# attiny85_breakout.net
KiCad netlist of a schematic drawn in EAGLE
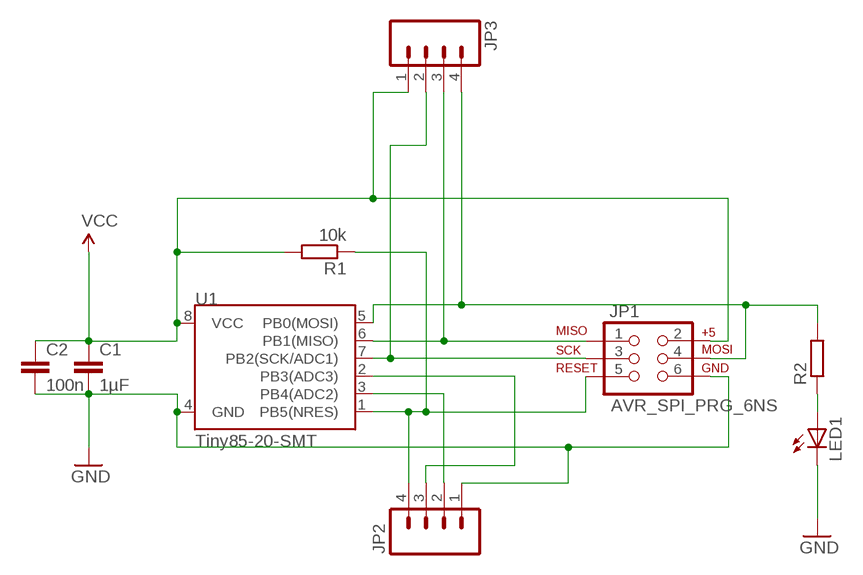
[diagram p0: schematic, sheet 1]

(export (version "E")
  (design (tool "Eeschema 10.0.6"))
  (components
    (comp (ref "C1")
      (value "1µF")
      (footprint "eagle-import:C0805")
      (libsource (lib "eagle-import") (part "C-EUC0805"))
    )
    (comp (ref "C2")
      (value "100n")
      (footprint "eagle-import:C0805")
      (libsource (lib "eagle-import") (part "C-EUC0805"))
    )
    (comp (ref "JP1")
      (value "AVR_SPI_PRG_6NS")
      (footprint "eagle-import:2X3-NS")
      (libsource (lib "eagle-import") (part "AVR_SPI_PRG_6NS"))
    )
    (comp (ref "JP2")
      (value "M04PTH")
      (footprint "eagle-import:1X04")
      (libsource (lib "eagle-import") (part "M04PTH"))
    )
    (comp (ref "JP3")
      (value "M04PTH")
      (footprint "eagle-import:1X04")
      (libsource (lib "eagle-import") (part "M04PTH"))
    )
    (comp (ref "LED1")
      (value "LEDCHIPLED_0805")
      (footprint "eagle-import:CHIPLED_0805")
      (libsource (lib "eagle-import") (part "LEDCHIPLED_0805"))
    )
    (comp (ref "R1")
      (value "10k")
      (footprint "eagle-import:R0805")
      (libsource (lib "eagle-import") (part "R-EU_R0805"))
    )
    (comp (ref "R2")
      (value "R-EU_R0603")
      (footprint "eagle-import:R0603")
      (libsource (lib "eagle-import") (part "R-EU_R0603"))
    )
    (comp (ref "U1")
      (value "Tiny85-20-SMT")
      (footprint "eagle-import:SO08-EIAJ")
      (libsource (lib "eagle-import") (part "ATTINY45TINY85-20-SMT"))
    )
  )
  (nets
    (net (code "1") (name "GND") (class "Default")
      (node (ref "C1") (pin "2") (pinfunction "2_2") (pintype "passive"))
      (node (ref "C2") (pin "2") (pinfunction "2_2") (pintype "passive"))
      (node (ref "JP1") (pin "6") (pinfunction "6_6") (pintype "passive"))
      (node (ref "JP2") (pin "1") (pinfunction "1_1") (pintype "passive"))
      (node (ref "LED1") (pin "C") (pinfunction "C_C") (pintype "passive"))
      (node (ref "U1") (pin "4") (pinfunction "GND_4") (pintype "bidirectional"))
    )
    (net (code "2") (name "Net-(LED1-PadA)") (class "Default")
      (node (ref "LED1") (pin "A") (pinfunction "A_A") (pintype "passive"))
      (node (ref "R2") (pin "1") (pinfunction "1_1") (pintype "passive"))
    )
    (net (code "3") (name "Net-(U1-PB0(MOSI))") (class "Default")
      (node (ref "JP1") (pin "4") (pinfunction "4_4") (pintype "passive"))
      (node (ref "JP3") (pin "4") (pinfunction "4_4") (pintype "passive"))
      (node (ref "R2") (pin "2") (pinfunction "2_2") (pintype "passive"))
      (node (ref "U1") (pin "5") (pinfunction "PB0(MOSI)_5") (pintype "bidirectional"))
    )
    (net (code "4") (name "Net-(U1-PB1(MISO))") (class "Default")
      (node (ref "JP1") (pin "1") (pinfunction "1_1") (pintype "passive"))
      (node (ref "JP3") (pin "3") (pinfunction "3_3") (pintype "passive"))
      (node (ref "U1") (pin "6") (pinfunction "PB1(MISO)_6") (pintype "bidirectional"))
    )
    (net (code "5") (name "Net-(U1-PB2(SCK{slash}ADC1))") (class "Default")
      (node (ref "JP1") (pin "3") (pinfunction "3_3") (pintype "passive"))
      (node (ref "JP3") (pin "2") (pinfunction "2_2") (pintype "passive"))
      (node (ref "U1") (pin "7") (pinfunction "PB2(SCK/ADC1)_7") (pintype "bidirectional"))
    )
    (net (code "6") (name "Net-(U1-PB3(ADC3))") (class "Default")
      (node (ref "JP2") (pin "3") (pinfunction "3_3") (pintype "passive"))
      (node (ref "U1") (pin "2") (pinfunction "PB3(ADC3)_2") (pintype "bidirectional"))
    )
    (net (code "7") (name "Net-(U1-PB4(ADC2))") (class "Default")
      (node (ref "JP2") (pin "2") (pinfunction "2_2") (pintype "passive"))
      (node (ref "U1") (pin "3") (pinfunction "PB4(ADC2)_3") (pintype "bidirectional"))
    )
    (net (code "8") (name "Net-(U1-PB5(NRES))") (class "Default")
      (node (ref "JP1") (pin "5") (pinfunction "5_5") (pintype "passive"))
      (node (ref "JP2") (pin "4") (pinfunction "4_4") (pintype "passive"))
      (node (ref "R1") (pin "1") (pinfunction "1_1") (pintype "passive"))
      (node (ref "U1") (pin "1") (pinfunction "PB5(NRES)_1") (pintype "bidirectional"))
    )
    (net (code "9") (name "VCC") (class "Default")
      (node (ref "C1") (pin "1") (pinfunction "1_1") (pintype "passive"))
      (node (ref "C2") (pin "1") (pinfunction "1_1") (pintype "passive"))
      (node (ref "JP1") (pin "2") (pinfunction "2_2") (pintype "passive"))
      (node (ref "JP3") (pin "1") (pinfunction "1_1") (pintype "passive"))
      (node (ref "R1") (pin "2") (pinfunction "2_2") (pintype "passive"))
      (node (ref "U1") (pin "8") (pinfunction "VCC_8") (pintype "bidirectional"))
    )
  )
)
